# 04_Microport_Host.net
KiCad netlist of a schematic drawn in Altium Designer
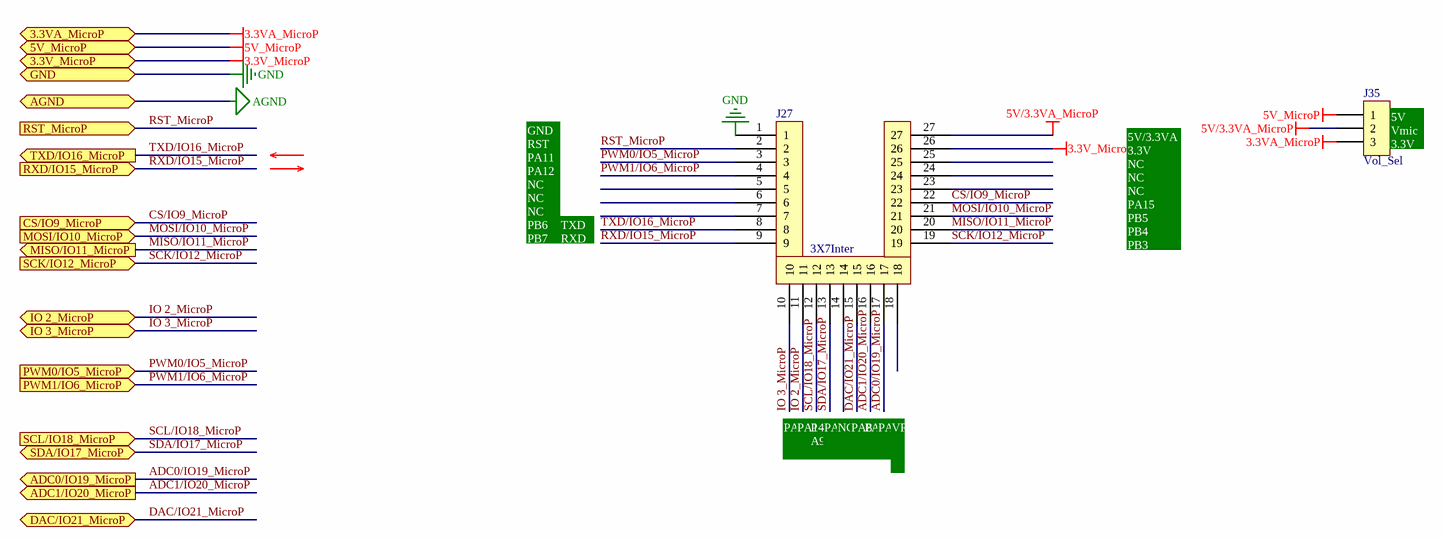
[diagram p0: 04.Microport_Host.SchDoc]

(export (version "E")
  (design (tool "Eeschema 10.0.6"))
  (components
    (comp (ref "J27") (value "3X7Inter") (footprint "SIP-27 2.54C") (libsource (lib "*") (part "3X7Inter")))
    (comp (ref "J35")
      (value "Vol_Sel")
      (footprint "SIP-3-2.54")
      (description "Connector")
      (libsource (lib "无需物料号元件") (part "CON3"))
    )
  )
  (nets
    (net (code "1") (name "/ADC0{slash}IO19_MicroP") (class "Default")
      (node (ref "J27") (pin "17") (pinfunction "17_17") (pintype "passive"))
    )
    (net (code "2") (name "/ADC1{slash}IO20_MicroP") (class "Default")
      (node (ref "J27") (pin "16") (pinfunction "16_16") (pintype "passive"))
    )
    (net (code "3") (name "/CS{slash}IO9_MicroP") (class "Default")
      (node (ref "J27") (pin "22") (pinfunction "22_22") (pintype "passive"))
    )
    (net (code "4") (name "/DAC{slash}IO21_MicroP") (class "Default")
      (node (ref "J27") (pin "15") (pinfunction "15_15") (pintype "passive"))
    )
    (net (code "5") (name "/IO 2_MicroP") (class "Default")
      (node (ref "J27") (pin "11") (pinfunction "11_11") (pintype "passive"))
    )
    (net (code "6") (name "/IO 3_MicroP") (class "Default")
      (node (ref "J27") (pin "10") (pinfunction "10_10") (pintype "passive"))
    )
    (net (code "7") (name "/MISO{slash}IO11_MicroP") (class "Default")
      (node (ref "J27") (pin "20") (pinfunction "20_20") (pintype "passive"))
    )
    (net (code "8") (name "/MOSI{slash}IO10_MicroP") (class "Default")
      (node (ref "J27") (pin "21") (pinfunction "21_21") (pintype "passive"))
    )
    (net (code "9") (name "/PWM0{slash}IO5_MicroP") (class "Default")
      (node (ref "J27") (pin "3") (pinfunction "3_3") (pintype "passive"))
    )
    (net (code "10") (name "/PWM1{slash}IO6_MicroP") (class "Default")
      (node (ref "J27") (pin "4") (pinfunction "4_4") (pintype "passive"))
    )
    (net (code "11") (name "/RST_MicroP") (class "Default")
      (node (ref "J27") (pin "2") (pinfunction "2_2") (pintype "passive"))
    )
    (net (code "12") (name "/RXD{slash}IO15_MicroP") (class "Default")
      (node (ref "J27") (pin "9") (pinfunction "9_9") (pintype "passive"))
    )
    (net (code "13") (name "/SCK{slash}IO12_MicroP") (class "Default")
      (node (ref "J27") (pin "19") (pinfunction "19_19") (pintype "passive"))
    )
    (net (code "14") (name "/SCL{slash}IO18_MicroP") (class "Default")
      (node (ref "J27") (pin "12") (pinfunction "12_12") (pintype "passive"))
    )
    (net (code "15") (name "/SDA{slash}IO17_MicroP") (class "Default")
      (node (ref "J27") (pin "13") (pinfunction "13_13") (pintype "passive"))
    )
    (net (code "16") (name "/TXD{slash}IO16_MicroP") (class "Default")
      (node (ref "J27") (pin "8") (pinfunction "8_8") (pintype "passive"))
    )
    (net (code "17") (name "3.3VA_MicroP") (class "Default")
      (node (ref "J35") (pin "3") (pinfunction "3_3") (pintype "passive"))
    )
    (net (code "18") (name "3.3V_MicroP") (class "Default")
      (node (ref "J27") (pin "26") (pinfunction "26_26") (pintype "passive"))
    )
    (net (code "19") (name "5V_MicroP") (class "Default")
      (node (ref "J35") (pin "1") (pinfunction "1_1") (pintype "passive"))
    )
    (net (code "20") (name "5V{slash}3.3VA_MicroP") (class "Default")
      (node (ref "J27") (pin "27") (pinfunction "27_27") (pintype "passive"))
      (node (ref "J35") (pin "2") (pinfunction "2_2") (pintype "passive"))
    )
    (net (code "22") (name "GND") (class "Default")
      (node (ref "J27") (pin "1") (pinfunction "1_1") (pintype "passive"))
    )
    (net (code "23") (name "unconnected-(J27-Pad5)") (class "Default")
      (node (ref "J27") (pin "5") (pinfunction "5_5") (pintype "passive"))
    )
    (net (code "24") (name "unconnected-(J27-Pad6)") (class "Default")
      (node (ref "J27") (pin "6") (pinfunction "6_6") (pintype "passive"))
    )
    (net (code "25") (name "unconnected-(J27-Pad7)") (class "Default")
      (node (ref "J27") (pin "7") (pinfunction "7_7") (pintype "passive"))
    )
    (net (code "26") (name "unconnected-(J27-Pad14)") (class "Default")
      (node (ref "J27") (pin "14") (pinfunction "14_14") (pintype "passive"))
    )
    (net (code "27") (name "unconnected-(J27-Pad18)") (class "Default")
      (node (ref "J27") (pin "18") (pinfunction "18_18") (pintype "passive"))
    )
    (net (code "28") (name "unconnected-(J27-Pad23)") (class "Default")
      (node (ref "J27") (pin "23") (pinfunction "23_23") (pintype "passive"))
    )
    (net (code "29") (name "unconnected-(J27-Pad24)") (class "Default")
      (node (ref "J27") (pin "24") (pinfunction "24_24") (pintype "passive"))
    )
    (net (code "30") (name "unconnected-(J27-Pad25)") (class "Default")
      (node (ref "J27") (pin "25") (pinfunction "25_25") (pintype "passive"))
    )
  )
)
